# SCH_VCCT.net
KiCad netlist of a schematic drawn in EasyEDA
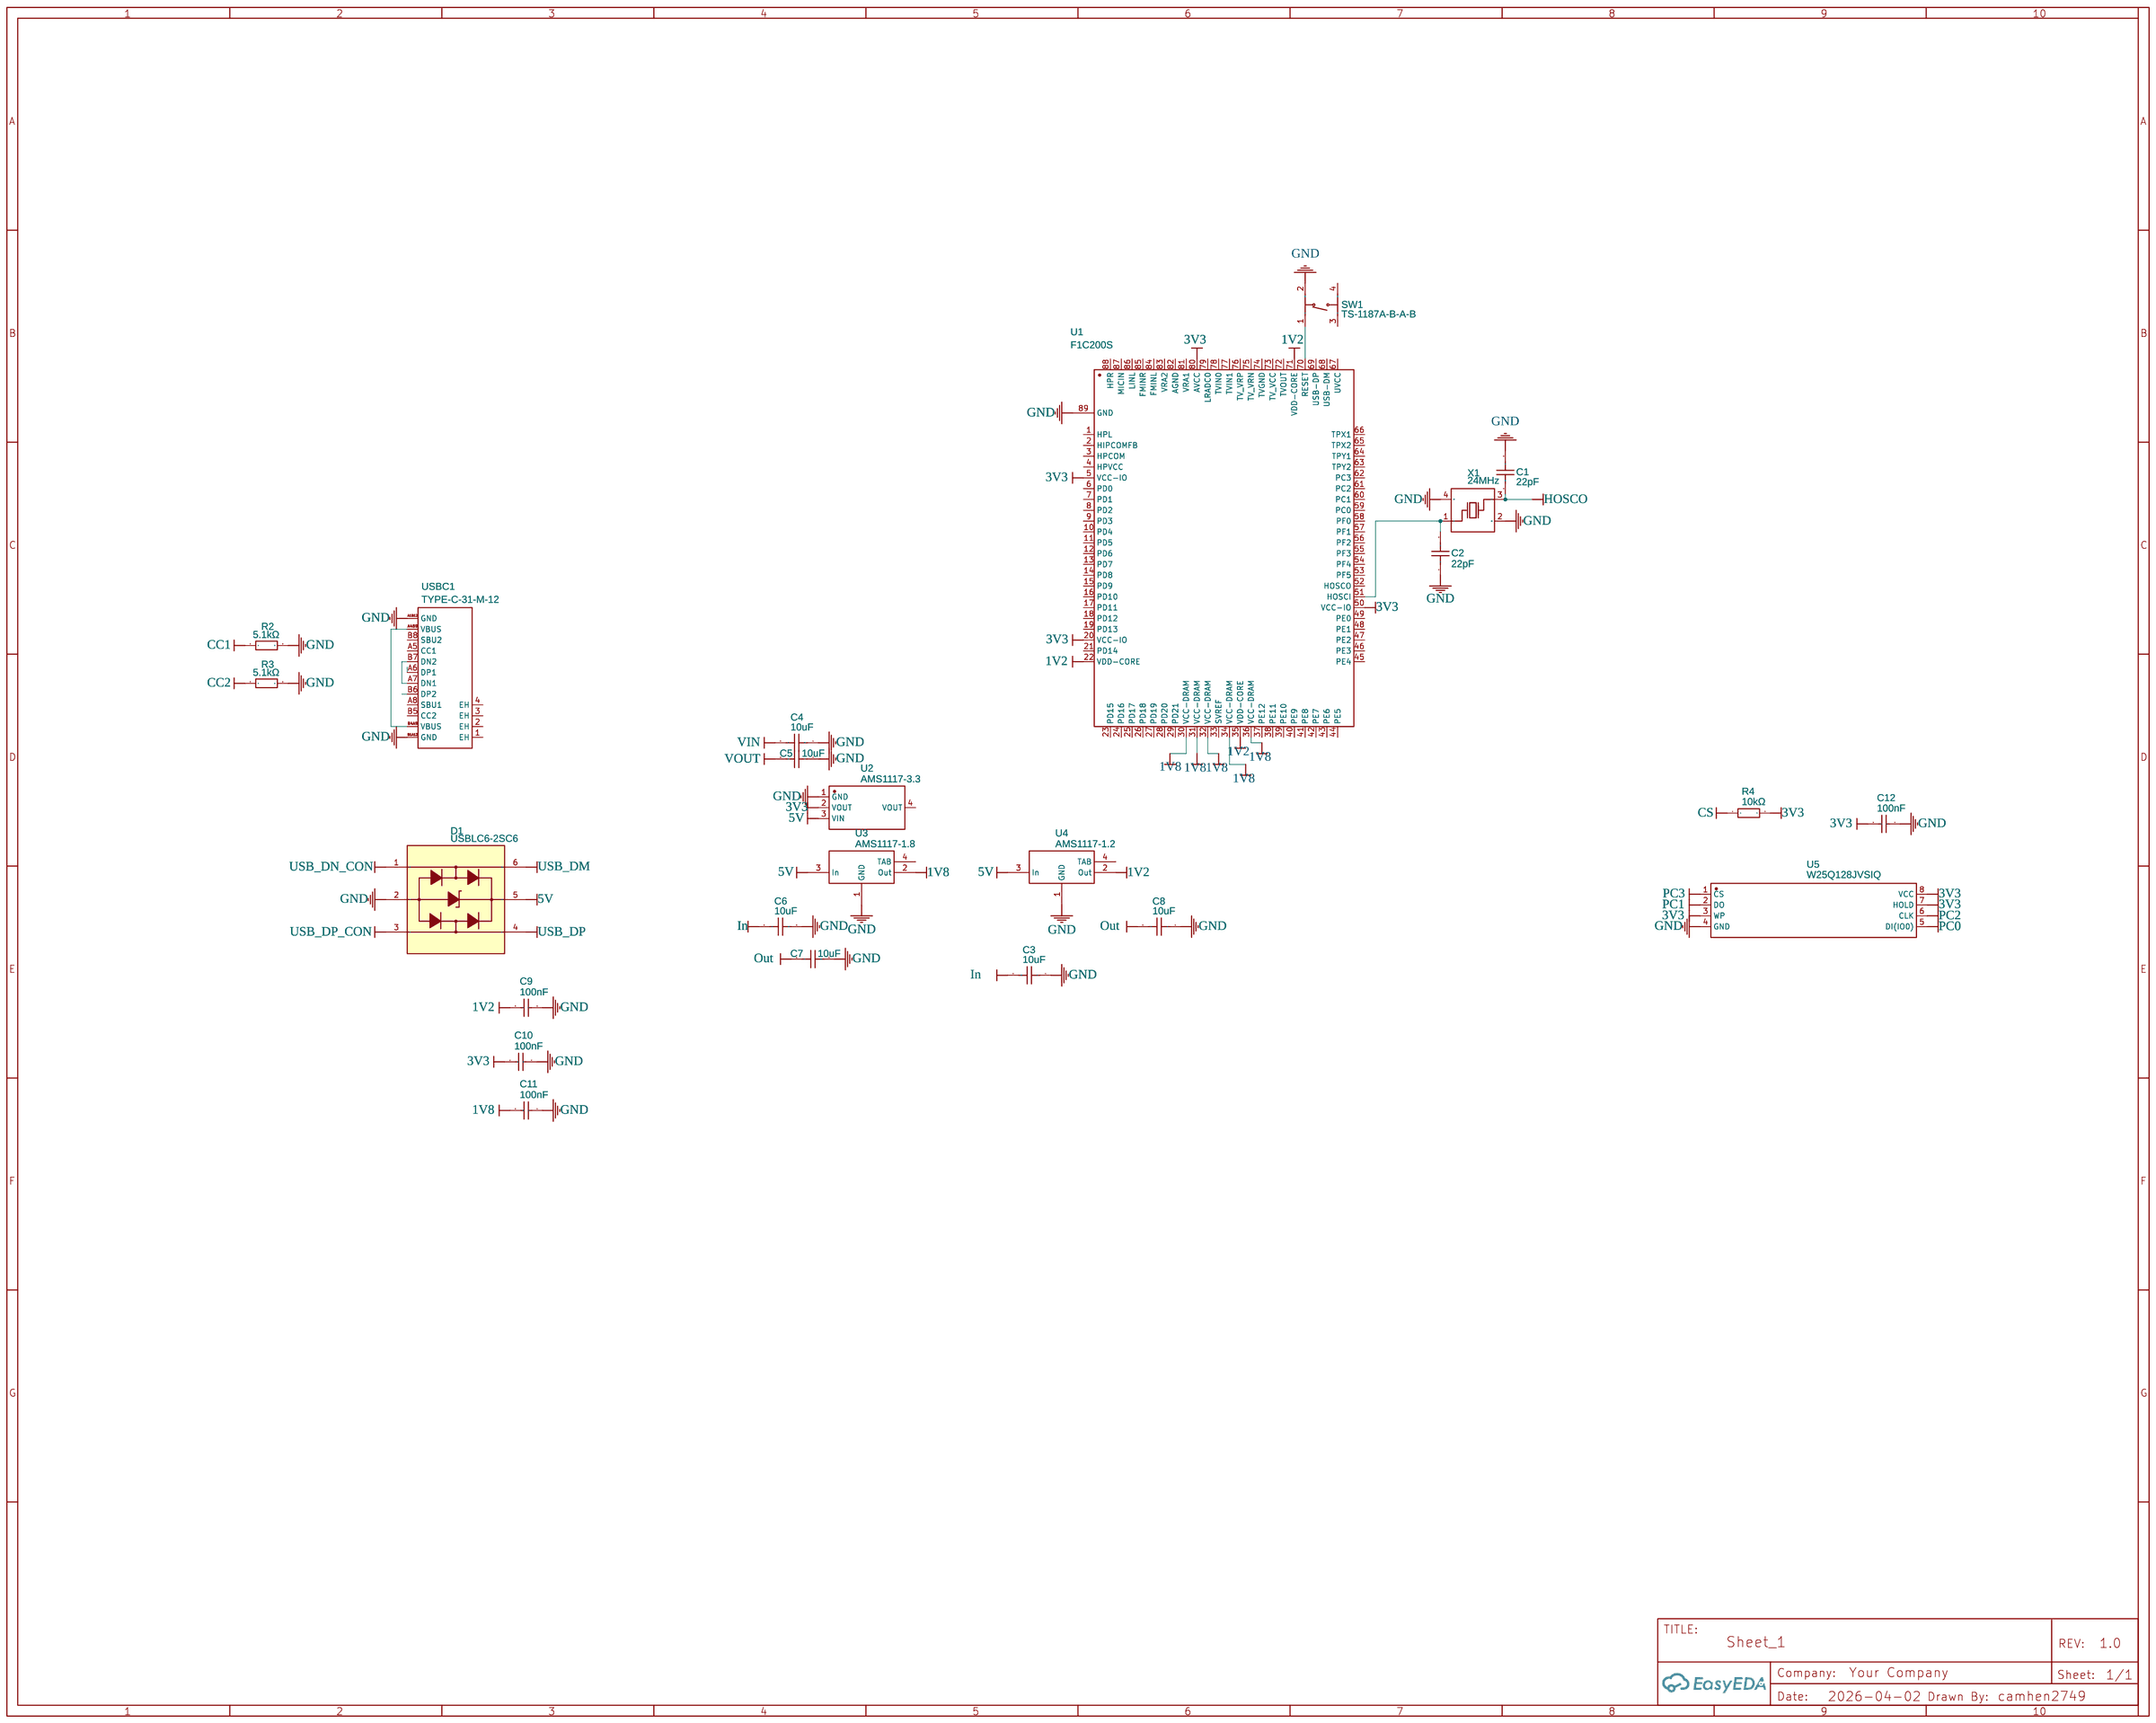
[diagram p0: schematic sheet]

(export (version "E")
  (design (tool "Eeschema 10.0.6"))
  (components
    (comp (ref "C1")
      (value "22pF")
      (fields (field (name "Manufacturer Part") "C1608CH2A220J080AA") (field (name "Manufacturer") "TDK"))
      (libsource (lib "") (part "C1608CH2A220J080AA"))
    )
    (comp (ref "C2")
      (value "22pF")
      (fields (field (name "Manufacturer Part") "C1608CH2A220J080AA") (field (name "Manufacturer") "TDK"))
      (libsource (lib "") (part "C1608CH2A220J080AA"))
    )
    (comp (ref "C3")
      (value "10uF")
      (fields
        (field (name "Manufacturer Part") "CC0603KRX5R6BB106")
        (field (name "Manufacturer") "YAGEO(国巨)")
      )
      (libsource (lib "") (part "CC0603KRX5R6BB106"))
    )
    (comp (ref "C4")
      (value "10uF")
      (fields
        (field (name "Manufacturer Part") "CC0603KRX5R6BB106")
        (field (name "Manufacturer") "YAGEO(国巨)")
      )
      (libsource (lib "") (part "CC0603KRX5R6BB106"))
    )
    (comp (ref "C5")
      (value "10uF")
      (fields
        (field (name "Manufacturer Part") "CC0603KRX5R6BB106")
        (field (name "Manufacturer") "YAGEO(国巨)")
      )
      (libsource (lib "") (part "CC0603KRX5R6BB106"))
    )
    (comp (ref "C6")
      (value "10uF")
      (fields
        (field (name "Manufacturer Part") "CC0603KRX5R6BB106")
        (field (name "Manufacturer") "YAGEO(国巨)")
      )
      (libsource (lib "") (part "CC0603KRX5R6BB106"))
    )
    (comp (ref "C7")
      (value "10uF")
      (fields
        (field (name "Manufacturer Part") "CC0603KRX5R6BB106")
        (field (name "Manufacturer") "YAGEO(国巨)")
      )
      (libsource (lib "") (part "CC0603KRX5R6BB106"))
    )
    (comp (ref "C8")
      (value "10uF")
      (fields
        (field (name "Manufacturer Part") "CC0603KRX5R6BB106")
        (field (name "Manufacturer") "YAGEO(国巨)")
      )
      (libsource (lib "") (part "CC0603KRX5R6BB106"))
    )
    (comp (ref "C9")
      (value "100nF")
      (fields
        (field (name "Manufacturer Part") "CC0402KRX7R9BB104")
        (field (name "Manufacturer") "YAGEO(国巨)")
      )
      (libsource (lib "") (part "CC0402KRX7R9BB104"))
    )
    (comp (ref "C10")
      (value "100nF")
      (fields
        (field (name "Manufacturer Part") "CC0402KRX7R9BB104")
        (field (name "Manufacturer") "YAGEO(国巨)")
      )
      (libsource (lib "") (part "CC0402KRX7R9BB104"))
    )
    (comp (ref "C11")
      (value "100nF")
      (fields
        (field (name "Manufacturer Part") "CC0402KRX7R9BB104")
        (field (name "Manufacturer") "YAGEO(国巨)")
      )
      (libsource (lib "") (part "CC0402KRX7R9BB104"))
    )
    (comp (ref "C12")
      (value "100nF")
      (fields
        (field (name "Manufacturer Part") "CC0402KRX7R9BB104")
        (field (name "Manufacturer") "YAGEO(国巨)")
      )
      (libsource (lib "") (part "CC0402KRX7R9BB104"))
    )
    (comp (ref "D1")
      (value "USBLC6-2SC6")
      (fields (field (name "Manufacturer") "ST(意法半导体)"))
      (libsource (lib "") (part "USBLC6-2SC6"))
    )
    (comp (ref "R2")
      (value "5.1kΩ")
      (fields (field (name "Manufacturer Part") "RC0402FR-075K1L") (field (name "Manufacturer") "YAGEO(国巨)"))
      (libsource (lib "") (part "RC0402FR-075K1L"))
    )
    (comp (ref "R3")
      (value "5.1kΩ")
      (fields (field (name "Manufacturer Part") "RC0402FR-075K1L") (field (name "Manufacturer") "YAGEO(国巨)"))
      (libsource (lib "") (part "RC0402FR-075K1L"))
    )
    (comp (ref "R4")
      (value "10kΩ")
      (fields (field (name "Manufacturer Part") "RC0402FR-0710KL") (field (name "Manufacturer") "YAGEO(国巨)"))
      (libsource (lib "") (part "RC0402FR-0710KL"))
    )
    (comp (ref "SW1")
      (value "TS-1187A-B-A-B")
      (fields (field (name "Manufacturer") "XKB Connection(中国星坤)"))
      (libsource (lib "") (part "TS-1187A-B-A-B"))
    )
    (comp (ref "U1")
      (value "F1C200S")
      (fields (field (name "Manufacturer") "Allwinner(全志)"))
      (libsource (lib "") (part "F1C200S"))
    )
    (comp (ref "U2")
      (value "AMS1117-3.3")
      (fields (field (name "Manufacturer") "AMS"))
      (libsource (lib "") (part "AMS1117-3.3"))
    )
    (comp (ref "U3")
      (value "AMS1117-1.8")
      (fields (field (name "Manufacturer") "AMS"))
      (libsource (lib "") (part "AMS1117-1.8"))
    )
    (comp (ref "U4")
      (value "AMS1117-1.2")
      (fields (field (name "Manufacturer") "AMS"))
      (libsource (lib "") (part "AMS1117-1.2"))
    )
    (comp (ref "U5")
      (value "W25Q128JVSIQ")
      (fields (field (name "Manufacturer") "Winbond(华邦)"))
      (libsource (lib "") (part "W25Q128JVSIQ"))
    )
    (comp (ref "USBC1")
      (value "TYPE-C-31-M-12")
      (fields (field (name "Manufacturer") "韩国韩荣"))
      (libsource (lib "") (part "TYPE-C-31-M-12"))
    )
    (comp (ref "X1")
      (value "24MHz")
      (fields (field (name "Manufacturer Part") "X322524MSB4SI") (field (name "Manufacturer") "YXC(扬兴晶振)"))
      (libsource (lib "") (part "X322524MSB4SI"))
    )
  )
  (nets
    (net (code "1") (name "1V2") (class "Default")
      (node (ref "C9") (pin "1") (pinfunction "1_1") (pintype "input"))
      (node (ref "U1") (pin "22") (pinfunction "VDD-CORE_22") (pintype "unspecified"))
      (node (ref "U1") (pin "35") (pinfunction "VDD-CORE_35") (pintype "unspecified"))
      (node (ref "U1") (pin "71") (pinfunction "VDD-CORE_71") (pintype "unspecified"))
      (node (ref "U4") (pin "2") (pinfunction "Out_2") (pintype "unspecified"))
    )
    (net (code "2") (name "1V8") (class "Default")
      (node (ref "C11") (pin "1") (pinfunction "1_1") (pintype "input"))
      (node (ref "U1") (pin "30") (pinfunction "VCC-DRAM_30") (pintype "unspecified"))
      (node (ref "U1") (pin "31") (pinfunction "VCC-DRAM_31") (pintype "unspecified"))
      (node (ref "U1") (pin "32") (pinfunction "VCC-DRAM_32") (pintype "unspecified"))
      (node (ref "U1") (pin "34") (pinfunction "VCC-DRAM_34") (pintype "unspecified"))
      (node (ref "U1") (pin "36") (pinfunction "VCC-DRAM_36") (pintype "unspecified"))
      (node (ref "U3") (pin "2") (pinfunction "Out_2") (pintype "unspecified"))
    )
    (net (code "3") (name "3V3") (class "Default")
      (node (ref "C10") (pin "1") (pinfunction "1_1") (pintype "input"))
      (node (ref "C12") (pin "1") (pinfunction "1_1") (pintype "input"))
      (node (ref "R4") (pin "2") (pinfunction "2_2") (pintype "input"))
      (node (ref "U1") (pin "20") (pinfunction "VCC-IO_20") (pintype "unspecified"))
      (node (ref "U1") (pin "5") (pinfunction "VCC-IO_5") (pintype "unspecified"))
      (node (ref "U1") (pin "50") (pinfunction "VCC-IO_50") (pintype "unspecified"))
      (node (ref "U1") (pin "80") (pinfunction "AVCC_80") (pintype "unspecified"))
      (node (ref "U2") (pin "2") (pinfunction "VOUT_2") (pintype "unspecified"))
      (node (ref "U5") (pin "3") (pinfunction "WP_3") (pintype "unspecified"))
      (node (ref "U5") (pin "7") (pinfunction "HOLD_7") (pintype "unspecified"))
      (node (ref "U5") (pin "8") (pinfunction "VCC_8") (pintype "unspecified"))
    )
    (net (code "4") (name "5V") (class "Default")
      (node (ref "D1") (pin "5") (pinfunction "5_5") (pintype "input"))
      (node (ref "U2") (pin "3") (pinfunction "VIN_3") (pintype "unspecified"))
      (node (ref "U3") (pin "3") (pinfunction "In_3") (pintype "unspecified"))
      (node (ref "U4") (pin "3") (pinfunction "In_3") (pintype "unspecified"))
    )
    (net (code "5") (name "CC1") (class "Default")
      (node (ref "R2") (pin "1") (pinfunction "1_1") (pintype "input"))
    )
    (net (code "6") (name "CC2") (class "Default")
      (node (ref "R3") (pin "1") (pinfunction "1_1") (pintype "input"))
    )
    (net (code "7") (name "CS") (class "Default")
      (node (ref "R4") (pin "1") (pinfunction "1_1") (pintype "input"))
    )
    (net (code "8") (name "GND") (class "Default")
      (node (ref "C1") (pin "2") (pinfunction "2_2") (pintype "unspecified"))
      (node (ref "C10") (pin "2") (pinfunction "2_2") (pintype "input"))
      (node (ref "C11") (pin "2") (pinfunction "2_2") (pintype "input"))
      (node (ref "C12") (pin "2") (pinfunction "2_2") (pintype "input"))
      (node (ref "C2") (pin "1") (pinfunction "1_1") (pintype "unspecified"))
      (node (ref "C3") (pin "1") (pinfunction "1_1") (pintype "unspecified"))
      (node (ref "C4") (pin "1") (pinfunction "1_1") (pintype "unspecified"))
      (node (ref "C5") (pin "1") (pinfunction "1_1") (pintype "unspecified"))
      (node (ref "C6") (pin "1") (pinfunction "1_1") (pintype "unspecified"))
      (node (ref "C7") (pin "1") (pinfunction "1_1") (pintype "unspecified"))
      (node (ref "C8") (pin "1") (pinfunction "1_1") (pintype "unspecified"))
      (node (ref "C9") (pin "2") (pinfunction "2_2") (pintype "input"))
      (node (ref "D1") (pin "2") (pinfunction "2_2") (pintype "input"))
      (node (ref "R2") (pin "2") (pinfunction "2_2") (pintype "input"))
      (node (ref "R3") (pin "2") (pinfunction "2_2") (pintype "input"))
      (node (ref "SW1") (pin "2") (pinfunction "B_2") (pintype "unspecified"))
      (node (ref "U1") (pin "89") (pinfunction "GND_89") (pintype "unspecified"))
      (node (ref "U2") (pin "1") (pinfunction "GND_1") (pintype "unspecified"))
      (node (ref "U3") (pin "1") (pinfunction "GND_1") (pintype "unspecified"))
      (node (ref "U4") (pin "1") (pinfunction "GND_1") (pintype "unspecified"))
      (node (ref "U5") (pin "4") (pinfunction "GND_4") (pintype "unspecified"))
      (node (ref "USBC1") (pin "A1B12") (pinfunction "GND_A1B12") (pintype "unspecified"))
      (node (ref "USBC1") (pin "B1A12") (pinfunction "GND_B1A12") (pintype "unspecified"))
      (node (ref "X1") (pin "2") (pinfunction "GND_2") (pintype "unspecified"))
      (node (ref "X1") (pin "4") (pinfunction "GND_4") (pintype "unspecified"))
    )
    (net (code "9") (name "HOSCO") (class "Default")
      (node (ref "C1") (pin "1") (pinfunction "1_1") (pintype "unspecified"))
      (node (ref "X1") (pin "3") (pinfunction "OSC2_3") (pintype "unspecified"))
    )
    (net (code "10") (name "In") (class "Default")
      (node (ref "C3") (pin "2") (pinfunction "2_2") (pintype "unspecified"))
      (node (ref "C6") (pin "2") (pinfunction "2_2") (pintype "unspecified"))
    )
    (net (code "11") (name "Net-(SW1-A)") (class "Default")
      (node (ref "SW1") (pin "1") (pinfunction "A_1") (pintype "unspecified"))
      (node (ref "U1") (pin "70") (pinfunction "RESET_70") (pintype "unspecified"))
    )
    (net (code "12") (name "Net-(U1-HOSCI)") (class "Default")
      (node (ref "C2") (pin "2") (pinfunction "2_2") (pintype "unspecified"))
      (node (ref "U1") (pin "51") (pinfunction "HOSCI_51") (pintype "unspecified"))
      (node (ref "X1") (pin "1") (pinfunction "OSC1_1") (pintype "unspecified"))
    )
    (net (code "13") (name "Net-(USBC1-DN1)") (class "Default")
      (node (ref "USBC1") (pin "A7") (pinfunction "DN1_A7") (pintype "unspecified"))
      (node (ref "USBC1") (pin "B7") (pinfunction "DN2_B7") (pintype "unspecified"))
    )
    (net (code "14") (name "Net-(USBC1-VBUS-PadA4B9)") (class "Default")
      (node (ref "USBC1") (pin "A4B9") (pinfunction "VBUS_A4B9") (pintype "unspecified"))
      (node (ref "USBC1") (pin "B4A9") (pinfunction "VBUS_B4A9") (pintype "unspecified"))
    )
    (net (code "15") (name "Out") (class "Default")
      (node (ref "C7") (pin "2") (pinfunction "2_2") (pintype "unspecified"))
      (node (ref "C8") (pin "2") (pinfunction "2_2") (pintype "unspecified"))
    )
    (net (code "16") (name "PC0") (class "Default")
      (node (ref "U5") (pin "5") (pinfunction "DI(IO0)_5") (pintype "unspecified"))
    )
    (net (code "17") (name "PC1") (class "Default")
      (node (ref "U5") (pin "2") (pinfunction "DO_2") (pintype "unspecified"))
    )
    (net (code "18") (name "PC2") (class "Default")
      (node (ref "U5") (pin "6") (pinfunction "CLK_6") (pintype "unspecified"))
    )
    (net (code "19") (name "PC3") (class "Default")
      (node (ref "U5") (pin "1") (pinfunction "CS_1") (pintype "unspecified"))
    )
    (net (code "20") (name "USB_DM") (class "Default")
      (node (ref "D1") (pin "6") (pinfunction "6_6") (pintype "input"))
    )
    (net (code "21") (name "USB_DN_CON") (class "Default")
      (node (ref "D1") (pin "1") (pinfunction "1_1") (pintype "input"))
    )
    (net (code "22") (name "USB_DP") (class "Default")
      (node (ref "D1") (pin "4") (pinfunction "4_4") (pintype "input"))
    )
    (net (code "23") (name "USB_DP_CON") (class "Default")
      (node (ref "D1") (pin "3") (pinfunction "3_3") (pintype "input"))
    )
    (net (code "24") (name "VIN") (class "Default")
      (node (ref "C4") (pin "2") (pinfunction "2_2") (pintype "unspecified"))
    )
    (net (code "25") (name "VOUT") (class "Default")
      (node (ref "C5") (pin "2") (pinfunction "2_2") (pintype "unspecified"))
    )
    (net (code "26") (name "unconnected-(SW1-C-Pad3)") (class "Default")
      (node (ref "SW1") (pin "3") (pinfunction "C_3") (pintype "unspecified"))
    )
    (net (code "27") (name "unconnected-(SW1-D-Pad4)") (class "Default")
      (node (ref "SW1") (pin "4") (pinfunction "D_4") (pintype "unspecified"))
    )
    (net (code "28") (name "unconnected-(U1-AGND-Pad82)") (class "Default")
      (node (ref "U1") (pin "82") (pinfunction "AGND_82") (pintype "unspecified"))
    )
    (net (code "29") (name "unconnected-(U1-FMINL-Pad84)") (class "Default")
      (node (ref "U1") (pin "84") (pinfunction "FMINL_84") (pintype "unspecified"))
    )
    (net (code "30") (name "unconnected-(U1-FMINR-Pad85)") (class "Default")
      (node (ref "U1") (pin "85") (pinfunction "FMINR_85") (pintype "unspecified"))
    )
    (net (code "31") (name "unconnected-(U1-HIPCOMFB-Pad2)") (class "Default")
      (node (ref "U1") (pin "2") (pinfunction "HIPCOMFB_2") (pintype "unspecified"))
    )
    (net (code "32") (name "unconnected-(U1-HOSCO-Pad52)") (class "Default")
      (node (ref "U1") (pin "52") (pinfunction "HOSCO_52") (pintype "unspecified"))
    )
    (net (code "33") (name "unconnected-(U1-HPCOM-Pad3)") (class "Default")
      (node (ref "U1") (pin "3") (pinfunction "HPCOM_3") (pintype "unspecified"))
    )
    (net (code "34") (name "unconnected-(U1-HPL-Pad1)") (class "Default")
      (node (ref "U1") (pin "1") (pinfunction "HPL_1") (pintype "unspecified"))
    )
    (net (code "35") (name "unconnected-(U1-HPR-Pad88)") (class "Default")
      (node (ref "U1") (pin "88") (pinfunction "HPR_88") (pintype "unspecified"))
    )
    (net (code "36") (name "unconnected-(U1-HPVCC-Pad4)") (class "Default")
      (node (ref "U1") (pin "4") (pinfunction "HPVCC_4") (pintype "unspecified"))
    )
    (net (code "37") (name "unconnected-(U1-LINL-Pad86)") (class "Default")
      (node (ref "U1") (pin "86") (pinfunction "LINL_86") (pintype "unspecified"))
    )
    (net (code "38") (name "unconnected-(U1-LRADC0-Pad79)") (class "Default")
      (node (ref "U1") (pin "79") (pinfunction "LRADC0_79") (pintype "unspecified"))
    )
    (net (code "39") (name "unconnected-(U1-MICIN-Pad87)") (class "Default")
      (node (ref "U1") (pin "87") (pinfunction "MICIN_87") (pintype "unspecified"))
    )
    (net (code "40") (name "unconnected-(U1-PC0-Pad59)") (class "Default")
      (node (ref "U1") (pin "59") (pinfunction "PC0_59") (pintype "unspecified"))
    )
    (net (code "41") (name "unconnected-(U1-PC1-Pad60)") (class "Default")
      (node (ref "U1") (pin "60") (pinfunction "PC1_60") (pintype "unspecified"))
    )
    (net (code "42") (name "unconnected-(U1-PC2-Pad61)") (class "Default")
      (node (ref "U1") (pin "61") (pinfunction "PC2_61") (pintype "unspecified"))
    )
    (net (code "43") (name "unconnected-(U1-PC3-Pad62)") (class "Default")
      (node (ref "U1") (pin "62") (pinfunction "PC3_62") (pintype "unspecified"))
    )
    (net (code "44") (name "unconnected-(U1-PD0-Pad6)") (class "Default")
      (node (ref "U1") (pin "6") (pinfunction "PD0_6") (pintype "unspecified"))
    )
    (net (code "45") (name "unconnected-(U1-PD1-Pad7)") (class "Default")
      (node (ref "U1") (pin "7") (pinfunction "PD1_7") (pintype "unspecified"))
    )
    (net (code "46") (name "unconnected-(U1-PD2-Pad8)") (class "Default")
      (node (ref "U1") (pin "8") (pinfunction "PD2_8") (pintype "unspecified"))
    )
    (net (code "47") (name "unconnected-(U1-PD3-Pad9)") (class "Default")
      (node (ref "U1") (pin "9") (pinfunction "PD3_9") (pintype "unspecified"))
    )
    (net (code "48") (name "unconnected-(U1-PD4-Pad10)") (class "Default")
      (node (ref "U1") (pin "10") (pinfunction "PD4_10") (pintype "unspecified"))
    )
    (net (code "49") (name "unconnected-(U1-PD5-Pad11)") (class "Default")
      (node (ref "U1") (pin "11") (pinfunction "PD5_11") (pintype "unspecified"))
    )
    (net (code "50") (name "unconnected-(U1-PD6-Pad12)") (class "Default")
      (node (ref "U1") (pin "12") (pinfunction "PD6_12") (pintype "unspecified"))
    )
    (net (code "51") (name "unconnected-(U1-PD7-Pad13)") (class "Default")
      (node (ref "U1") (pin "13") (pinfunction "PD7_13") (pintype "unspecified"))
    )
    (net (code "52") (name "unconnected-(U1-PD8-Pad14)") (class "Default")
      (node (ref "U1") (pin "14") (pinfunction "PD8_14") (pintype "unspecified"))
    )
    (net (code "53") (name "unconnected-(U1-PD9-Pad15)") (class "Default")
      (node (ref "U1") (pin "15") (pinfunction "PD9_15") (pintype "unspecified"))
    )
    (net (code "54") (name "unconnected-(U1-PD10-Pad16)") (class "Default")
      (node (ref "U1") (pin "16") (pinfunction "PD10_16") (pintype "unspecified"))
    )
    (net (code "55") (name "unconnected-(U1-PD11-Pad17)") (class "Default")
      (node (ref "U1") (pin "17") (pinfunction "PD11_17") (pintype "unspecified"))
    )
    (net (code "56") (name "unconnected-(U1-PD12-Pad18)") (class "Default")
      (node (ref "U1") (pin "18") (pinfunction "PD12_18") (pintype "unspecified"))
    )
    (net (code "57") (name "unconnected-(U1-PD13-Pad19)") (class "Default")
      (node (ref "U1") (pin "19") (pinfunction "PD13_19") (pintype "unspecified"))
    )
    (net (code "58") (name "unconnected-(U1-PD14-Pad21)") (class "Default")
      (node (ref "U1") (pin "21") (pinfunction "PD14_21") (pintype "unspecified"))
    )
    (net (code "59") (name "unconnected-(U1-PD15-Pad23)") (class "Default")
      (node (ref "U1") (pin "23") (pinfunction "PD15_23") (pintype "unspecified"))
    )
    (net (code "60") (name "unconnected-(U1-PD16-Pad24)") (class "Default")
      (node (ref "U1") (pin "24") (pinfunction "PD16_24") (pintype "unspecified"))
    )
    (net (code "61") (name "unconnected-(U1-PD17-Pad25)") (class "Default")
      (node (ref "U1") (pin "25") (pinfunction "PD17_25") (pintype "unspecified"))
    )
    (net (code "62") (name "unconnected-(U1-PD18-Pad26)") (class "Default")
      (node (ref "U1") (pin "26") (pinfunction "PD18_26") (pintype "unspecified"))
    )
    (net (code "63") (name "unconnected-(U1-PD19-Pad27)") (class "Default")
      (node (ref "U1") (pin "27") (pinfunction "PD19_27") (pintype "unspecified"))
    )
    (net (code "64") (name "unconnected-(U1-PD20-Pad28)") (class "Default")
      (node (ref "U1") (pin "28") (pinfunction "PD20_28") (pintype "unspecified"))
    )
    (net (code "65") (name "unconnected-(U1-PD21-Pad29)") (class "Default")
      (node (ref "U1") (pin "29") (pinfunction "PD21_29") (pintype "unspecified"))
    )
    (net (code "66") (name "unconnected-(U1-PE0-Pad49)") (class "Default")
      (node (ref "U1") (pin "49") (pinfunction "PE0_49") (pintype "unspecified"))
    )
    (net (code "67") (name "unconnected-(U1-PE1-Pad48)") (class "Default")
      (node (ref "U1") (pin "48") (pinfunction "PE1_48") (pintype "unspecified"))
    )
    (net (code "68") (name "unconnected-(U1-PE2-Pad47)") (class "Default")
      (node (ref "U1") (pin "47") (pinfunction "PE2_47") (pintype "unspecified"))
    )
    (net (code "69") (name "unconnected-(U1-PE3-Pad46)") (class "Default")
      (node (ref "U1") (pin "46") (pinfunction "PE3_46") (pintype "unspecified"))
    )
    (net (code "70") (name "unconnected-(U1-PE4-Pad45)") (class "Default")
      (node (ref "U1") (pin "45") (pinfunction "PE4_45") (pintype "unspecified"))
    )
    (net (code "71") (name "unconnected-(U1-PE5-Pad44)") (class "Default")
      (node (ref "U1") (pin "44") (pinfunction "PE5_44") (pintype "unspecified"))
    )
    (net (code "72") (name "unconnected-(U1-PE6-Pad43)") (class "Default")
      (node (ref "U1") (pin "43") (pinfunction "PE6_43") (pintype "unspecified"))
    )
    (net (code "73") (name "unconnected-(U1-PE7-Pad42)") (class "Default")
      (node (ref "U1") (pin "42") (pinfunction "PE7_42") (pintype "unspecified"))
    )
    (net (code "74") (name "unconnected-(U1-PE8-Pad41)") (class "Default")
      (node (ref "U1") (pin "41") (pinfunction "PE8_41") (pintype "unspecified"))
    )
    (net (code "75") (name "unconnected-(U1-PE9-Pad40)") (class "Default")
      (node (ref "U1") (pin "40") (pinfunction "PE9_40") (pintype "unspecified"))
    )
    (net (code "76") (name "unconnected-(U1-PE10-Pad39)") (class "Default")
      (node (ref "U1") (pin "39") (pinfunction "PE10_39") (pintype "unspecified"))
    )
    (net (code "77") (name "unconnected-(U1-PE11-Pad38)") (class "Default")
      (node (ref "U1") (pin "38") (pinfunction "PE11_38") (pintype "unspecified"))
    )
    (net (code "78") (name "unconnected-(U1-PE12-Pad37)") (class "Default")
      (node (ref "U1") (pin "37") (pinfunction "PE12_37") (pintype "unspecified"))
    )
    (net (code "79") (name "unconnected-(U1-PF0-Pad58)") (class "Default")
      (node (ref "U1") (pin "58") (pinfunction "PF0_58") (pintype "unspecified"))
    )
    (net (code "80") (name "unconnected-(U1-PF1-Pad57)") (class "Default")
      (node (ref "U1") (pin "57") (pinfunction "PF1_57") (pintype "unspecified"))
    )
    (net (code "81") (name "unconnected-(U1-PF2-Pad56)") (class "Default")
      (node (ref "U1") (pin "56") (pinfunction "PF2_56") (pintype "unspecified"))
    )
    (net (code "82") (name "unconnected-(U1-PF3-Pad55)") (class "Default")
      (node (ref "U1") (pin "55") (pinfunction "PF3_55") (pintype "unspecified"))
    )
    (net (code "83") (name "unconnected-(U1-PF4-Pad54)") (class "Default")
      (node (ref "U1") (pin "54") (pinfunction "PF4_54") (pintype "unspecified"))
    )
    (net (code "84") (name "unconnected-(U1-PF5-Pad53)") (class "Default")
      (node (ref "U1") (pin "53") (pinfunction "PF5_53") (pintype "unspecified"))
    )
    (net (code "85") (name "unconnected-(U1-SVREF-Pad33)") (class "Default")
      (node (ref "U1") (pin "33") (pinfunction "SVREF_33") (pintype "unspecified"))
    )
    (net (code "86") (name "unconnected-(U1-TPX1-Pad66)") (class "Default")
      (node (ref "U1") (pin "66") (pinfunction "TPX1_66") (pintype "unspecified"))
    )
    (net (code "87") (name "unconnected-(U1-TPX2-Pad65)") (class "Default")
      (node (ref "U1") (pin "65") (pinfunction "TPX2_65") (pintype "unspecified"))
    )
    (net (code "88") (name "unconnected-(U1-TPY1-Pad64)") (class "Default")
      (node (ref "U1") (pin "64") (pinfunction "TPY1_64") (pintype "unspecified"))
    )
    (net (code "89") (name "unconnected-(U1-TPY2-Pad63)") (class "Default")
      (node (ref "U1") (pin "63") (pinfunction "TPY2_63") (pintype "unspecified"))
    )
    (net (code "90") (name "unconnected-(U1-TVGND-Pad74)") (class "Default")
      (node (ref "U1") (pin "74") (pinfunction "TVGND_74") (pintype "unspecified"))
    )
    (net (code "91") (name "unconnected-(U1-TVIN0-Pad78)") (class "Default")
      (node (ref "U1") (pin "78") (pinfunction "TVIN0_78") (pintype "unspecified"))
    )
    (net (code "92") (name "unconnected-(U1-TVIN1-Pad77)") (class "Default")
      (node (ref "U1") (pin "77") (pinfunction "TVIN1_77") (pintype "unspecified"))
    )
    (net (code "93") (name "unconnected-(U1-TVOUT-Pad72)") (class "Default")
      (node (ref "U1") (pin "72") (pinfunction "TVOUT_72") (pintype "unspecified"))
    )
    (net (code "94") (name "unconnected-(U1-TV_VCC-Pad73)") (class "Default")
      (node (ref "U1") (pin "73") (pinfunction "TV_VCC_73") (pintype "unspecified"))
    )
    (net (code "95") (name "unconnected-(U1-TV_VRN-Pad75)") (class "Default")
      (node (ref "U1") (pin "75") (pinfunction "TV_VRN_75") (pintype "unspecified"))
    )
    (net (code "96") (name "unconnected-(U1-TV_VRP-Pad76)") (class "Default")
      (node (ref "U1") (pin "76") (pinfunction "TV_VRP_76") (pintype "unspecified"))
    )
    (net (code "97") (name "unconnected-(U1-USB-DM-Pad68)") (class "Default")
      (node (ref "U1") (pin "68") (pinfunction "USB-DM_68") (pintype "unspecified"))
    )
    (net (code "98") (name "unconnected-(U1-USB-DP-Pad69)") (class "Default")
      (node (ref "U1") (pin "69") (pinfunction "USB-DP_69") (pintype "unspecified"))
    )
    (net (code "99") (name "unconnected-(U1-UVCC-Pad67)") (class "Default")
      (node (ref "U1") (pin "67") (pinfunction "UVCC_67") (pintype "unspecified"))
    )
    (net (code "100") (name "unconnected-(U1-VRA1-Pad81)") (class "Default")
      (node (ref "U1") (pin "81") (pinfunction "VRA1_81") (pintype "unspecified"))
    )
    (net (code "101") (name "unconnected-(U1-VRA2-Pad83)") (class "Default")
      (node (ref "U1") (pin "83") (pinfunction "VRA2_83") (pintype "unspecified"))
    )
    (net (code "102") (name "unconnected-(U2-VOUT-Pad4)") (class "Default")
      (node (ref "U2") (pin "4") (pinfunction "VOUT_4") (pintype "unspecified"))
    )
    (net (code "103") (name "unconnected-(U3-TAB-Pad4)") (class "Default")
      (node (ref "U3") (pin "4") (pinfunction "TAB_4") (pintype "unspecified"))
    )
    (net (code "104") (name "unconnected-(U4-TAB-Pad4)") (class "Default")
      (node (ref "U4") (pin "4") (pinfunction "TAB_4") (pintype "unspecified"))
    )
    (net (code "105") (name "unconnected-(USBC1-CC1-PadA5)") (class "Default")
      (node (ref "USBC1") (pin "A5") (pinfunction "CC1_A5") (pintype "unspecified"))
    )
    (net (code "106") (name "unconnected-(USBC1-CC2-PadB5)") (class "Default")
      (node (ref "USBC1") (pin "B5") (pinfunction "CC2_B5") (pintype "unspecified"))
    )
    (net (code "107") (name "unconnected-(USBC1-DP1-PadA6)") (class "Default")
      (node (ref "USBC1") (pin "A6") (pinfunction "DP1_A6") (pintype "unspecified"))
    )
    (net (code "108") (name "unconnected-(USBC1-DP2-PadB6)") (class "Default")
      (node (ref "USBC1") (pin "B6") (pinfunction "DP2_B6") (pintype "unspecified"))
    )
    (net (code "109") (name "unconnected-(USBC1-EH-Pad1)") (class "Default")
      (node (ref "USBC1") (pin "1") (pinfunction "EH_1") (pintype "unspecified"))
    )
    (net (code "110") (name "unconnected-(USBC1-EH-Pad2)") (class "Default")
      (node (ref "USBC1") (pin "2") (pinfunction "EH_2") (pintype "unspecified"))
    )
    (net (code "111") (name "unconnected-(USBC1-EH-Pad3)") (class "Default")
      (node (ref "USBC1") (pin "3") (pinfunction "EH_3") (pintype "unspecified"))
    )
    (net (code "112") (name "unconnected-(USBC1-EH-Pad4)") (class "Default")
      (node (ref "USBC1") (pin "4") (pinfunction "EH_4") (pintype "unspecified"))
    )
    (net (code "113") (name "unconnected-(USBC1-SBU1-PadA8)") (class "Default")
      (node (ref "USBC1") (pin "A8") (pinfunction "SBU1_A8") (pintype "unspecified"))
    )
    (net (code "114") (name "unconnected-(USBC1-SBU2-PadB8)") (class "Default")
      (node (ref "USBC1") (pin "B8") (pinfunction "SBU2_B8") (pintype "unspecified"))
    )
  )
)
